# Sensorsboard.net
KiCad netlist of a schematic drawn in EAGLE
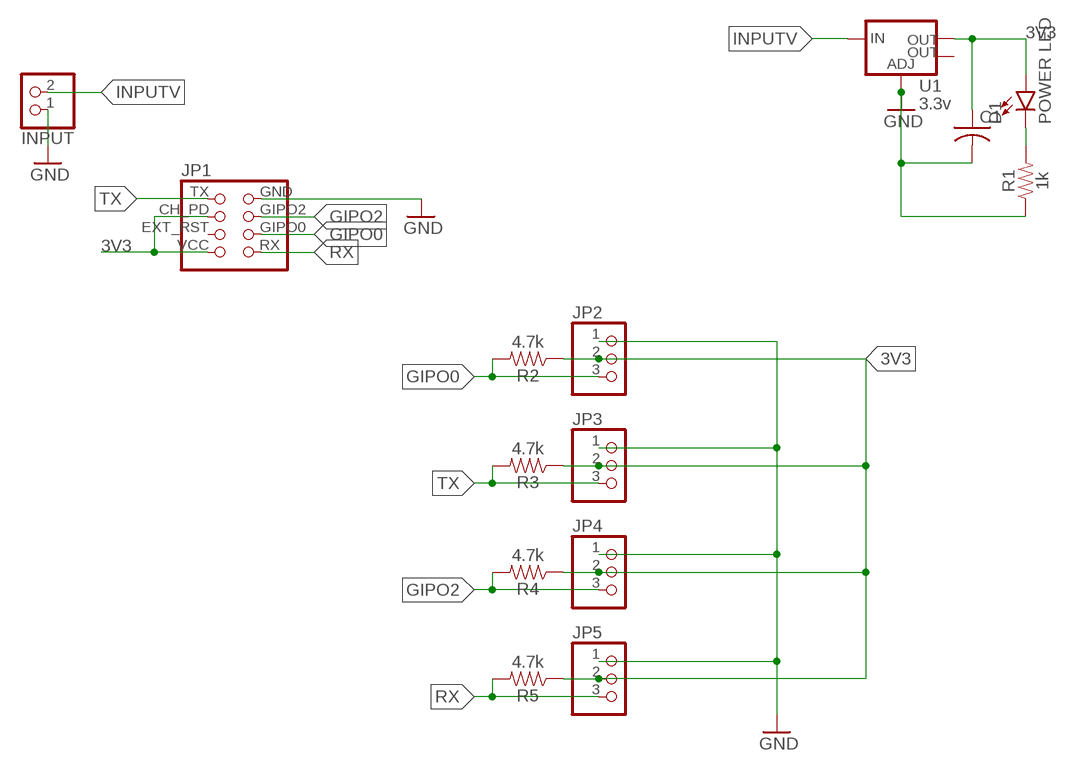
[diagram p0: schematic, sheet 1]

(export (version "E")
  (design (tool "Eeschema 10.0.6"))
  (components
    (comp (ref "C1")
      (value "C-USC1206K")
      (footprint "eagle-import:C1206K")
      (libsource (lib "eagle-import") (part "C-USC1206K"))
    )
    (comp (ref "D1")
      (value "POWER LED")
      (footprint "eagle-import:LED-0805")
      (libsource (lib "eagle-import") (part "LED-BLUE0805"))
    )
    (comp (ref "INPUT")
      (value "PINHD-1X2")
      (footprint "eagle-import:1X02")
      (libsource (lib "eagle-import") (part "PINHD-1X2"))
    )
    (comp (ref "JP1")
      (value "ESP-01-FEMALE")
      (footprint "eagle-import:ESP-01-FEMALE")
      (libsource (lib "eagle-import") (part "ESP-01-FEMALE"))
    )
    (comp (ref "JP2")
      (value "PINHD-1X3")
      (footprint "eagle-import:1X03")
      (libsource (lib "eagle-import") (part "PINHD-1X3"))
    )
    (comp (ref "JP3")
      (value "PINHD-1X3")
      (footprint "eagle-import:1X03")
      (libsource (lib "eagle-import") (part "PINHD-1X3"))
    )
    (comp (ref "JP4")
      (value "PINHD-1X3")
      (footprint "eagle-import:1X03")
      (libsource (lib "eagle-import") (part "PINHD-1X3"))
    )
    (comp (ref "JP5")
      (value "PINHD-1X3")
      (footprint "eagle-import:1X03")
      (libsource (lib "eagle-import") (part "PINHD-1X3"))
    )
    (comp (ref "R1")
      (value "1k")
      (footprint "eagle-import:0805")
      (libsource (lib "eagle-import") (part "RESISTOR0805"))
    )
    (comp (ref "R2")
      (value "4.7k")
      (footprint "eagle-import:0805")
      (libsource (lib "eagle-import") (part "RESISTOR0805"))
    )
    (comp (ref "R3")
      (value "4.7k")
      (footprint "eagle-import:0805")
      (libsource (lib "eagle-import") (part "RESISTOR0805"))
    )
    (comp (ref "R4")
      (value "4.7k")
      (footprint "eagle-import:0805")
      (libsource (lib "eagle-import") (part "RESISTOR0805"))
    )
    (comp (ref "R5")
      (value "4.7k")
      (footprint "eagle-import:0805")
      (libsource (lib "eagle-import") (part "RESISTOR0805"))
    )
    (comp (ref "U1")
      (value "3.3v")
      (footprint "eagle-import:SOT223")
      (libsource (lib "eagle-import") (part "V_REG_LM1117SOT223"))
    )
  )
  (nets
    (net (code "1") (name "3V3") (class "Default")
      (node (ref "C1") (pin "1") (pinfunction "1_1") (pintype "passive"))
      (node (ref "D1") (pin "+") (pinfunction "A_+") (pintype "passive"))
      (node (ref "JP1") (pin "CH_PD") (pinfunction "CHIP_EN_CH_PD") (pintype "passive"))
      (node (ref "JP1") (pin "VCC") (pinfunction "VCC_VCC") (pintype "passive"))
      (node (ref "JP2") (pin "2") (pinfunction "2_2") (pintype "passive"))
      (node (ref "JP3") (pin "2") (pinfunction "2_2") (pintype "passive"))
      (node (ref "JP4") (pin "2") (pinfunction "2_2") (pintype "passive"))
      (node (ref "JP5") (pin "2") (pinfunction "2_2") (pintype "passive"))
      (node (ref "R2") (pin "1") (pinfunction "1_1") (pintype "passive"))
      (node (ref "R3") (pin "1") (pinfunction "1_1") (pintype "passive"))
      (node (ref "R4") (pin "1") (pinfunction "1_1") (pintype "passive"))
      (node (ref "R5") (pin "1") (pinfunction "1_1") (pintype "passive"))
      (node (ref "U1") (pin "2") (pinfunction "OUT_2") (pintype "output"))
    )
    (net (code "2") (name "GIPO0") (class "Default")
      (node (ref "JP1") (pin "GIPO0") (pinfunction "GIPO0_GIPO0") (pintype "passive"))
      (node (ref "JP2") (pin "3") (pinfunction "3_3") (pintype "passive"))
      (node (ref "R2") (pin "2") (pinfunction "2_2") (pintype "passive"))
    )
    (net (code "3") (name "GIPO2") (class "Default")
      (node (ref "JP1") (pin "GIPO2") (pinfunction "GIPO2_GIPO2") (pintype "passive"))
      (node (ref "JP4") (pin "3") (pinfunction "3_3") (pintype "passive"))
      (node (ref "R4") (pin "2") (pinfunction "2_2") (pintype "passive"))
    )
    (net (code "4") (name "GND") (class "Default")
      (node (ref "C1") (pin "2") (pinfunction "2_2") (pintype "passive"))
      (node (ref "INPUT") (pin "1") (pinfunction "1_1") (pintype "passive"))
      (node (ref "JP1") (pin "GND") (pinfunction "GND_GND") (pintype "passive"))
      (node (ref "JP2") (pin "1") (pinfunction "1_1") (pintype "passive"))
      (node (ref "JP3") (pin "1") (pinfunction "1_1") (pintype "passive"))
      (node (ref "JP4") (pin "1") (pinfunction "1_1") (pintype "passive"))
      (node (ref "JP5") (pin "1") (pinfunction "1_1") (pintype "passive"))
      (node (ref "R1") (pin "1") (pinfunction "1_1") (pintype "passive"))
      (node (ref "U1") (pin "1") (pinfunction "ADJ_1") (pintype "input"))
    )
    (net (code "5") (name "INPUTV") (class "Default")
      (node (ref "INPUT") (pin "2") (pinfunction "2_2") (pintype "passive"))
      (node (ref "U1") (pin "3") (pinfunction "IN_3") (pintype "input"))
    )
    (net (code "6") (name "Net-(D1-C)") (class "Default")
      (node (ref "D1") (pin "-") (pinfunction "C_-") (pintype "passive"))
      (node (ref "R1") (pin "2") (pinfunction "2_2") (pintype "passive"))
    )
    (net (code "7") (name "RX") (class "Default")
      (node (ref "JP1") (pin "RX") (pinfunction "RX_RX") (pintype "passive"))
      (node (ref "JP5") (pin "3") (pinfunction "3_3") (pintype "passive"))
      (node (ref "R5") (pin "2") (pinfunction "2_2") (pintype "passive"))
    )
    (net (code "8") (name "TX") (class "Default")
      (node (ref "JP1") (pin "TX") (pinfunction "TX_TX") (pintype "passive"))
      (node (ref "JP3") (pin "3") (pinfunction "3_3") (pintype "passive"))
      (node (ref "R3") (pin "2") (pinfunction "2_2") (pintype "passive"))
    )
    (net (code "9") (name "unconnected-(JP1-PadEXT_RST)") (class "Default")
      (node (ref "JP1") (pin "EXT_RST") (pinfunction "EXT_RST_EXT_RST") (pintype "passive"))
    )
    (net (code "10") (name "unconnected-(U1-OUT-Pad4)") (class "Default")
      (node (ref "U1") (pin "4") (pinfunction "OUT_4") (pintype "output"))
    )
  )
)
